# tft.net
KiCad netlist of a schematic drawn in EAGLE
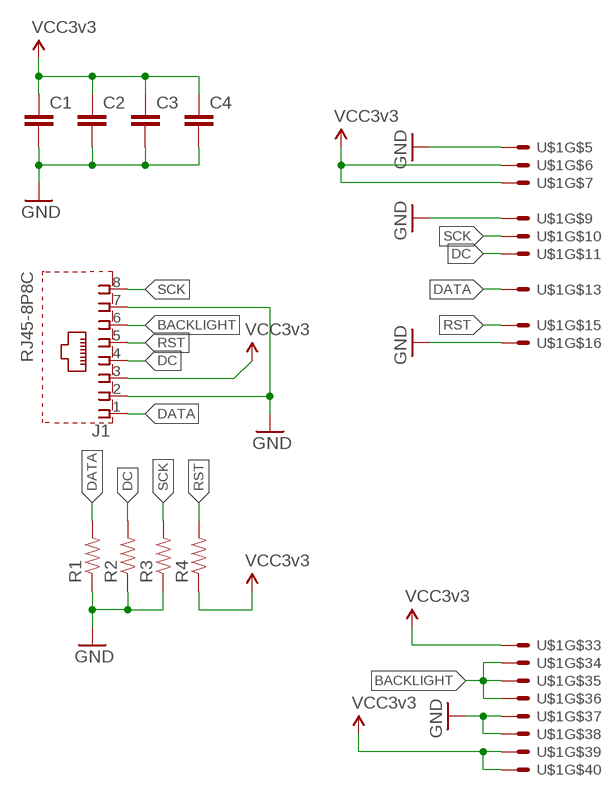
[diagram p0: schematic, sheet 1]

(export (version "E")
  (design (tool "Eeschema 10.0.6"))
  (components
    (comp (ref "C1")
      (value "CAP1206")
      (footprint "eagle-import:1206")
      (libsource (lib "eagle-import") (part "CAP1206"))
    )
    (comp (ref "C2")
      (value "CAP1206")
      (footprint "eagle-import:1206")
      (libsource (lib "eagle-import") (part "CAP1206"))
    )
    (comp (ref "C3")
      (value "CAP1206")
      (footprint "eagle-import:1206")
      (libsource (lib "eagle-import") (part "CAP1206"))
    )
    (comp (ref "C4")
      (value "CAP1206")
      (footprint "eagle-import:1206")
      (libsource (lib "eagle-import") (part "CAP1206"))
    )
    (comp (ref "J1")
      (value "RJ45-8P8C")
      (footprint "eagle-import:54602-908LF")
      (fields (field (name "PARTNO") "54602-908LF"))
      (libsource (lib "eagle-import") (part "RJ45-8P8C"))
    )
    (comp (ref "R1")
      (value "RESISTOR0603")
      (footprint "eagle-import:0603-RES")
      (libsource (lib "eagle-import") (part "RESISTOR0603"))
    )
    (comp (ref "R2")
      (value "RESISTOR0603")
      (footprint "eagle-import:0603-RES")
      (libsource (lib "eagle-import") (part "RESISTOR0603"))
    )
    (comp (ref "R3")
      (value "RESISTOR0603")
      (footprint "eagle-import:0603-RES")
      (libsource (lib "eagle-import") (part "RESISTOR0603"))
    )
    (comp (ref "R4")
      (value "RESISTOR0603")
      (footprint "eagle-import:0603-RES")
      (libsource (lib "eagle-import") (part "RESISTOR0603"))
    )
    (comp (ref "U$1")
      (value "XF2M-4015-WONKY")
      (footprint "eagle-import:XF2M-4015-WONKY")
      (libsource (lib "eagle-import") (part "XF2M-4015-WONKY"))
    )
  )
  (nets
    (net (code "1") (name "BACKLIGHT") (class "Default")
      (node (ref "J1") (pin "6") (pinfunction "6_6") (pintype "passive"))
      (node (ref "U$1") (pin "34") (pinfunction "MS_34") (pintype "passive"))
      (node (ref "U$1") (pin "35") (pinfunction "MS_35") (pintype "passive"))
      (node (ref "U$1") (pin "36") (pinfunction "MS_36") (pintype "passive"))
    )
    (net (code "2") (name "DATA") (class "Default")
      (node (ref "J1") (pin "1") (pinfunction "1_1") (pintype "passive"))
      (node (ref "R1") (pin "2") (pinfunction "2_2") (pintype "passive"))
      (node (ref "U$1") (pin "13") (pinfunction "MS_13") (pintype "passive"))
    )
    (net (code "3") (name "DC") (class "Default")
      (node (ref "J1") (pin "4") (pinfunction "4_4") (pintype "passive"))
      (node (ref "R2") (pin "2") (pinfunction "2_2") (pintype "passive"))
      (node (ref "U$1") (pin "11") (pinfunction "MS_11") (pintype "passive"))
    )
    (net (code "4") (name "GND") (class "Default")
      (node (ref "C1") (pin "2") (pinfunction "2_2") (pintype "passive"))
      (node (ref "C2") (pin "2") (pinfunction "2_2") (pintype "passive"))
      (node (ref "C3") (pin "2") (pinfunction "2_2") (pintype "passive"))
      (node (ref "C4") (pin "2") (pinfunction "2_2") (pintype "passive"))
      (node (ref "J1") (pin "2") (pinfunction "2_2") (pintype "passive"))
      (node (ref "J1") (pin "7") (pinfunction "7_7") (pintype "passive"))
      (node (ref "R1") (pin "1") (pinfunction "1_1") (pintype "passive"))
      (node (ref "R2") (pin "1") (pinfunction "1_1") (pintype "passive"))
      (node (ref "R3") (pin "1") (pinfunction "1_1") (pintype "passive"))
      (node (ref "U$1") (pin "16") (pinfunction "MS_16") (pintype "passive"))
      (node (ref "U$1") (pin "37") (pinfunction "MS_37") (pintype "passive"))
      (node (ref "U$1") (pin "38") (pinfunction "MS_38") (pintype "passive"))
      (node (ref "U$1") (pin "5") (pinfunction "MS_5") (pintype "passive"))
      (node (ref "U$1") (pin "9") (pinfunction "MS_9") (pintype "passive"))
    )
    (net (code "5") (name "RST") (class "Default")
      (node (ref "J1") (pin "5") (pinfunction "5_5") (pintype "passive"))
      (node (ref "R4") (pin "2") (pinfunction "2_2") (pintype "passive"))
      (node (ref "U$1") (pin "15") (pinfunction "MS_15") (pintype "passive"))
    )
    (net (code "6") (name "SCK") (class "Default")
      (node (ref "J1") (pin "8") (pinfunction "8_8") (pintype "passive"))
      (node (ref "R3") (pin "2") (pinfunction "2_2") (pintype "passive"))
      (node (ref "U$1") (pin "10") (pinfunction "MS_10") (pintype "passive"))
    )
    (net (code "7") (name "VCC3v3") (class "Default")
      (node (ref "C1") (pin "1") (pinfunction "1_1") (pintype "passive"))
      (node (ref "C2") (pin "1") (pinfunction "1_1") (pintype "passive"))
      (node (ref "C3") (pin "1") (pinfunction "1_1") (pintype "passive"))
      (node (ref "C4") (pin "1") (pinfunction "1_1") (pintype "passive"))
      (node (ref "J1") (pin "3") (pinfunction "3_3") (pintype "passive"))
      (node (ref "R4") (pin "1") (pinfunction "1_1") (pintype "passive"))
      (node (ref "U$1") (pin "33") (pinfunction "MS_33") (pintype "passive"))
      (node (ref "U$1") (pin "39") (pinfunction "MS_39") (pintype "passive"))
      (node (ref "U$1") (pin "40") (pinfunction "MS_40") (pintype "passive"))
      (node (ref "U$1") (pin "6") (pinfunction "MS_6") (pintype "passive"))
      (node (ref "U$1") (pin "7") (pinfunction "MS_7") (pintype "passive"))
    )
  )
)
